# linear_current_regulator.net
KiCad netlist of a schematic drawn in EAGLE
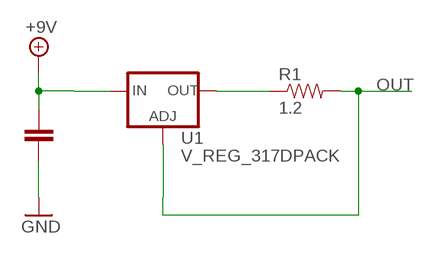
[diagram p0: schematic, sheet 1]

(export (version "E")
  (design (tool "Eeschema 10.0.6"))
  (components
    (comp (ref "C1")
      (value "0.1uF")
      (footprint "eagle-import:0402-CAP")
      (libsource (lib "eagle-import") (part "CAP0402-CAP"))
    )
    (comp (ref "R1")
      (value "1.2")
      (footprint "eagle-import:0402-RES")
      (libsource (lib "eagle-import") (part "RESISTOR0402-RES"))
    )
    (comp (ref "U1")
      (value "V_REG_317DPACK")
      (footprint "eagle-import:V-REG_DPACK")
      (libsource (lib "eagle-import") (part "V_REG_317DPACK"))
    )
  )
  (nets
    (net (code "1") (name "+9V") (class "Default")
      (node (ref "C1") (pin "1") (pinfunction "1_1") (pintype "passive"))
      (node (ref "U1") (pin "3") (pinfunction "IN_3") (pintype "input"))
    )
    (net (code "2") (name "/OUT") (class "Default")
      (node (ref "R1") (pin "2") (pinfunction "2_2") (pintype "passive"))
      (node (ref "U1") (pin "1") (pinfunction "ADJ_1") (pintype "input"))
    )
    (net (code "3") (name "GND") (class "Default")
      (node (ref "C1") (pin "2") (pinfunction "2_2") (pintype "passive"))
    )
    (net (code "4") (name "Net-(U1-OUT)") (class "Default")
      (node (ref "R1") (pin "1") (pinfunction "1_1") (pintype "passive"))
      (node (ref "U1") (pin "4") (pinfunction "OUT_4") (pintype "output"))
    )
  )
)
